# Filter_Capacitors_-_Port_L.net
KiCad netlist of a schematic drawn in Altium Designer
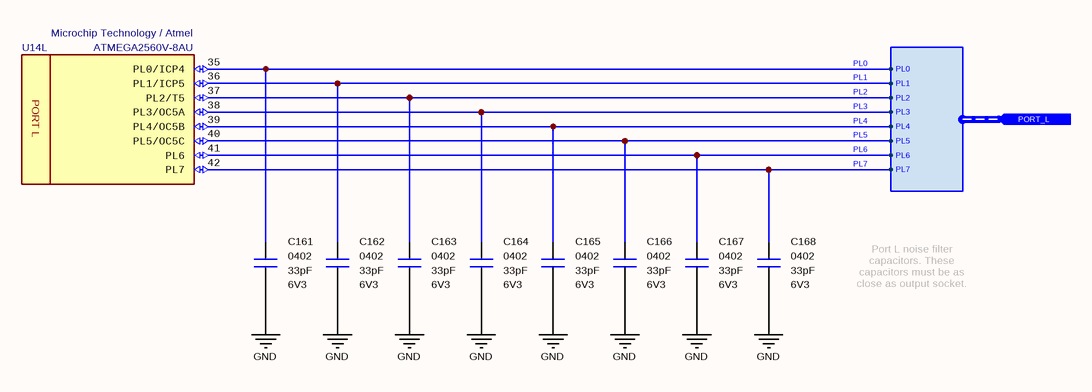
[diagram p0: Filter Capacitors - Port L.SchDoc]

(export (version "E")
  (design (tool "Eeschema 10.0.6"))
  (components
    (comp (ref "C161")
      (value "33pF")
      (footprint "CAPACITOR_0402")
      (description "Capacitor - 33pF [0402] (Ceramic)")
      (fields
        (field (name "TOLERANCE") "10%")
        (field (name "CASE") "0402")
        (field (name "VOLTAGE") "6V3")
        (field (name "MANUFACTURER PART NUMBER") "C0402C330J9RACAUTO")
      )
      (libsource (lib "Ovoo_Library") (part "Capacitor - 33pF [0402-6V3]"))
    )
    (comp (ref "C162")
      (value "33pF")
      (footprint "CAPACITOR_0402")
      (description "Capacitor - 33pF [0402] (Ceramic)")
      (fields
        (field (name "TOLERANCE") "10%")
        (field (name "CASE") "0402")
        (field (name "VOLTAGE") "6V3")
        (field (name "MANUFACTURER PART NUMBER") "C0402C330J9RACAUTO")
      )
      (libsource (lib "Ovoo_Library") (part "Capacitor - 33pF [0402-6V3]"))
    )
    (comp (ref "C163")
      (value "33pF")
      (footprint "CAPACITOR_0402")
      (description "Capacitor - 33pF [0402] (Ceramic)")
      (fields
        (field (name "TOLERANCE") "10%")
        (field (name "CASE") "0402")
        (field (name "VOLTAGE") "6V3")
        (field (name "MANUFACTURER PART NUMBER") "C0402C330J9RACAUTO")
      )
      (libsource (lib "Ovoo_Library") (part "Capacitor - 33pF [0402-6V3]"))
    )
    (comp (ref "C164")
      (value "33pF")
      (footprint "CAPACITOR_0402")
      (description "Capacitor - 33pF [0402] (Ceramic)")
      (fields
        (field (name "TOLERANCE") "10%")
        (field (name "CASE") "0402")
        (field (name "VOLTAGE") "6V3")
        (field (name "MANUFACTURER PART NUMBER") "C0402C330J9RACAUTO")
      )
      (libsource (lib "Ovoo_Library") (part "Capacitor - 33pF [0402-6V3]"))
    )
    (comp (ref "C165")
      (value "33pF")
      (footprint "CAPACITOR_0402")
      (description "Capacitor - 33pF [0402] (Ceramic)")
      (fields
        (field (name "TOLERANCE") "10%")
        (field (name "CASE") "0402")
        (field (name "VOLTAGE") "6V3")
        (field (name "MANUFACTURER PART NUMBER") "C0402C330J9RACAUTO")
      )
      (libsource (lib "Ovoo_Library") (part "Capacitor - 33pF [0402-6V3]"))
    )
    (comp (ref "C166")
      (value "33pF")
      (footprint "CAPACITOR_0402")
      (description "Capacitor - 33pF [0402] (Ceramic)")
      (fields
        (field (name "TOLERANCE") "10%")
        (field (name "CASE") "0402")
        (field (name "VOLTAGE") "6V3")
        (field (name "MANUFACTURER PART NUMBER") "C0402C330J9RACAUTO")
      )
      (libsource (lib "Ovoo_Library") (part "Capacitor - 33pF [0402-6V3]"))
    )
    (comp (ref "C167")
      (value "33pF")
      (footprint "CAPACITOR_0402")
      (description "Capacitor - 33pF [0402] (Ceramic)")
      (fields
        (field (name "TOLERANCE") "10%")
        (field (name "CASE") "0402")
        (field (name "VOLTAGE") "6V3")
        (field (name "MANUFACTURER PART NUMBER") "C0402C330J9RACAUTO")
      )
      (libsource (lib "Ovoo_Library") (part "Capacitor - 33pF [0402-6V3]"))
    )
    (comp (ref "C168")
      (value "33pF")
      (footprint "CAPACITOR_0402")
      (description "Capacitor - 33pF [0402] (Ceramic)")
      (fields
        (field (name "TOLERANCE") "10%")
        (field (name "CASE") "0402")
        (field (name "VOLTAGE") "6V3")
        (field (name "MANUFACTURER PART NUMBER") "C0402C330J9RACAUTO")
      )
      (libsource (lib "Ovoo_Library") (part "Capacitor - 33pF [0402-6V3]"))
    )
    (comp (ref "U14")
      (value "8-bit MicroController")
      (footprint "TQFP100")
      (description "8-bit Microcontrollers - MCU 256kB Flash 4kB EEPROM 86 I/O Pins")
      (fields
        (field (name "MANUFACTURER PART NUMBER") "ATMEGA2560V-8AU")
        (field (name "MANUFACTURER NAME") "Microchip Technology / Atmel")
      )
      (libsource (lib "Ovoo_Library") (part "IC - ATMEGA2560V-8AU"))
    )
  )
  (nets
    (net (code "2") (name "/PL0") (class "Default")
      (node (ref "C161") (pin "2") (pinfunction "2_2") (pintype "passive"))
      (node (ref "U14") (pin "35") (pinfunction "PL0/ICP4_35") (pintype "bidirectional"))
    )
    (net (code "3") (name "/PL1") (class "Default")
      (node (ref "C162") (pin "2") (pinfunction "2_2") (pintype "passive"))
      (node (ref "U14") (pin "36") (pinfunction "PL1/ICP5_36") (pintype "bidirectional"))
    )
    (net (code "4") (name "/PL2") (class "Default")
      (node (ref "C163") (pin "2") (pinfunction "2_2") (pintype "passive"))
      (node (ref "U14") (pin "37") (pinfunction "PL2/T5_37") (pintype "bidirectional"))
    )
    (net (code "5") (name "/PL3") (class "Default")
      (node (ref "C164") (pin "2") (pinfunction "2_2") (pintype "passive"))
      (node (ref "U14") (pin "38") (pinfunction "PL3/OC5A_38") (pintype "bidirectional"))
    )
    (net (code "6") (name "/PL4") (class "Default")
      (node (ref "C165") (pin "2") (pinfunction "2_2") (pintype "passive"))
      (node (ref "U14") (pin "39") (pinfunction "PL4/OC5B_39") (pintype "bidirectional"))
    )
    (net (code "7") (name "/PL5") (class "Default")
      (node (ref "C166") (pin "2") (pinfunction "2_2") (pintype "passive"))
      (node (ref "U14") (pin "40") (pinfunction "PL5/OC5C_40") (pintype "bidirectional"))
    )
    (net (code "8") (name "/PL6") (class "Default")
      (node (ref "C167") (pin "2") (pinfunction "2_2") (pintype "passive"))
      (node (ref "U14") (pin "41") (pinfunction "PL6_41") (pintype "bidirectional"))
    )
    (net (code "9") (name "/PL7") (class "Default")
      (node (ref "C168") (pin "2") (pinfunction "2_2") (pintype "passive"))
      (node (ref "U14") (pin "42") (pinfunction "PL7_42") (pintype "bidirectional"))
    )
    (net (code "11") (name "GND") (class "Default")
      (node (ref "C161") (pin "1") (pinfunction "1_1") (pintype "passive"))
      (node (ref "C162") (pin "1") (pinfunction "1_1") (pintype "passive"))
      (node (ref "C163") (pin "1") (pinfunction "1_1") (pintype "passive"))
      (node (ref "C164") (pin "1") (pinfunction "1_1") (pintype "passive"))
      (node (ref "C165") (pin "1") (pinfunction "1_1") (pintype "passive"))
      (node (ref "C166") (pin "1") (pinfunction "1_1") (pintype "passive"))
      (node (ref "C167") (pin "1") (pinfunction "1_1") (pintype "passive"))
      (node (ref "C168") (pin "1") (pinfunction "1_1") (pintype "passive"))
    )
  )
)
